# Sch.net
KiCad netlist of a schematic drawn in Altium Designer
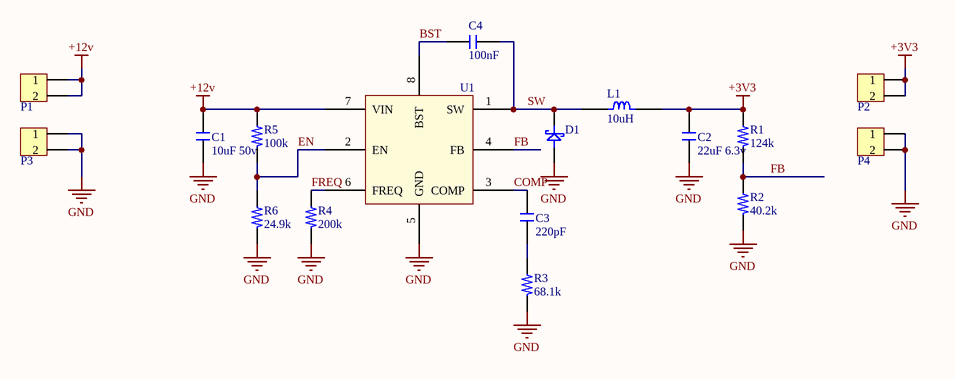
[diagram p0: Sch.SchDoc]

(export (version "E")
  (design (tool "Eeschema 10.0.6"))
  (components
    (comp (ref "C1") (value "10uF 50v") (footprint "C805") (libsource (lib "Custom_Sch") (part "C0805")))
    (comp (ref "C2") (value "22uF 6.3v") (footprint "C805") (libsource (lib "Custom_Sch") (part "C0805")))
    (comp (ref "C3") (value "220pF") (footprint "C805") (libsource (lib "Custom_Sch") (part "C0805")))
    (comp (ref "C4") (value "100nF") (footprint "C805") (libsource (lib "Custom_Sch") (part "C0805")))
    (comp (ref "D1")
      (value "SS34")
      (footprint "SS14(SMA)")
      (libsource (lib "Custom_Sch") (part "SS14(DO-214AA)"))
    )
    (comp (ref "L1")
      (value "10uH")
      (footprint "Inductor 12x12")
      (libsource (lib "Sch_Lib") (part "Inductor 12x12"))
    )
    (comp (ref "P1")
      (value "Pin Header 2x1,2.54mm")
      (footprint "PCBComponent_1")
      (libsource (lib "Sepehr library") (part "Pin Header 2x1,2.54mm"))
    )
    (comp (ref "P2")
      (value "Pin Header 2x1,2.54mm")
      (footprint "PCBComponent_1")
      (libsource (lib "Sepehr library") (part "Pin Header 2x1,2.54mm"))
    )
    (comp (ref "P3")
      (value "Pin Header 2x1,2.54mm")
      (footprint "PCBComponent_1")
      (libsource (lib "Sepehr library") (part "Pin Header 2x1,2.54mm"))
    )
    (comp (ref "P4")
      (value "Pin Header 2x1,2.54mm")
      (footprint "PCBComponent_1")
      (libsource (lib "Sepehr library") (part "Pin Header 2x1,2.54mm"))
    )
    (comp (ref "R1") (value "124k") (footprint "R805") (libsource (lib "Custom_Sch") (part "R0805")))
    (comp (ref "R2") (value "40.2k") (footprint "R805") (libsource (lib "Custom_Sch") (part "R0805")))
    (comp (ref "R3") (value "68.1k") (footprint "R805") (libsource (lib "Custom_Sch") (part "R0805")))
    (comp (ref "R4") (value "200k") (footprint "R805") (libsource (lib "Custom_Sch") (part "R0805")))
    (comp (ref "R5") (value "100k") (footprint "R805") (libsource (lib "Custom_Sch") (part "R0805")))
    (comp (ref "R6") (value "24.9k") (footprint "R805") (libsource (lib "Custom_Sch") (part "R0805")))
    (comp (ref "U1")
      (value "MP1584EN-LF")
      (footprint "MP1584")
      (description "Switching Voltage Regulators 3A 1.5MHz 28V Nonsync Buck")
      (fields (field (name "MANUFACTURER") "Monolithic Power Systems"))
      (libsource (lib "Custom_Sch") (part "MP1584EN-LF"))
    )
  )
  (nets
    (net (code "1") (name "+3V3") (class "Default")
      (node (ref "C2") (pin "2") (pinfunction "2_2") (pintype "passive"))
      (node (ref "L1") (pin "2") (pinfunction "2_2") (pintype "passive"))
      (node (ref "P2") (pin "1") (pinfunction "1_1") (pintype "passive"))
      (node (ref "P2") (pin "2") (pinfunction "2_2") (pintype "passive"))
      (node (ref "R1") (pin "1") (pinfunction "1_1") (pintype "passive"))
    )
    (net (code "2") (name "+12v") (class "Default")
      (node (ref "C1") (pin "2") (pinfunction "2_2") (pintype "passive"))
      (node (ref "P1") (pin "1") (pinfunction "1_1") (pintype "passive"))
      (node (ref "P1") (pin "2") (pinfunction "2_2") (pintype "passive"))
      (node (ref "R5") (pin "1") (pinfunction "1_1") (pintype "passive"))
      (node (ref "U1") (pin "7") (pinfunction "VIN_7") (pintype "passive"))
    )
    (net (code "3") (name "/BST") (class "Default")
      (node (ref "C4") (pin "1") (pinfunction "1_1") (pintype "passive"))
      (node (ref "U1") (pin "8") (pinfunction "BST_8") (pintype "passive"))
    )
    (net (code "4") (name "/COMP") (class "Default")
      (node (ref "C3") (pin "2") (pinfunction "2_2") (pintype "passive"))
      (node (ref "U1") (pin "3") (pinfunction "COMP_3") (pintype "passive"))
    )
    (net (code "5") (name "/EN") (class "Default")
      (node (ref "R5") (pin "2") (pinfunction "2_2") (pintype "passive"))
      (node (ref "R6") (pin "1") (pinfunction "1_1") (pintype "passive"))
      (node (ref "U1") (pin "2") (pinfunction "EN_2") (pintype "passive"))
    )
    (net (code "6") (name "/FB") (class "Default")
      (node (ref "R1") (pin "2") (pinfunction "2_2") (pintype "passive"))
      (node (ref "R2") (pin "1") (pinfunction "1_1") (pintype "passive"))
      (node (ref "U1") (pin "4") (pinfunction "FB_4") (pintype "passive"))
    )
    (net (code "7") (name "/FREQ") (class "Default")
      (node (ref "R4") (pin "1") (pinfunction "1_1") (pintype "passive"))
      (node (ref "U1") (pin "6") (pinfunction "FREQ_6") (pintype "passive"))
    )
    (net (code "8") (name "/SW") (class "Default")
      (node (ref "C4") (pin "2") (pinfunction "2_2") (pintype "passive"))
      (node (ref "D1") (pin "K") (pinfunction "2_K") (pintype "passive"))
      (node (ref "L1") (pin "1") (pinfunction "1_1") (pintype "passive"))
      (node (ref "U1") (pin "1") (pinfunction "SW_1") (pintype "passive"))
    )
    (net (code "9") (name "GND") (class "Default")
      (node (ref "C1") (pin "1") (pinfunction "1_1") (pintype "passive"))
      (node (ref "C2") (pin "1") (pinfunction "1_1") (pintype "passive"))
      (node (ref "D1") (pin "A") (pinfunction "1_A") (pintype "passive"))
      (node (ref "P3") (pin "1") (pinfunction "1_1") (pintype "passive"))
      (node (ref "P3") (pin "2") (pinfunction "2_2") (pintype "passive"))
      (node (ref "P4") (pin "1") (pinfunction "1_1") (pintype "passive"))
      (node (ref "P4") (pin "2") (pinfunction "2_2") (pintype "passive"))
      (node (ref "R2") (pin "2") (pinfunction "2_2") (pintype "passive"))
      (node (ref "R3") (pin "2") (pinfunction "2_2") (pintype "passive"))
      (node (ref "R4") (pin "2") (pinfunction "2_2") (pintype "passive"))
      (node (ref "R6") (pin "2") (pinfunction "2_2") (pintype "passive"))
      (node (ref "U1") (pin "5") (pinfunction "GND_5") (pintype "passive"))
    )
    (net (code "10") (name "Net-(C3-Pad1)") (class "Default")
      (node (ref "C3") (pin "1") (pinfunction "1_1") (pintype "passive"))
      (node (ref "R3") (pin "1") (pinfunction "1_1") (pintype "passive"))
    )
  )
)
